# Ampli_FI2.net
KiCad netlist of a schematic drawn in Altium Designer
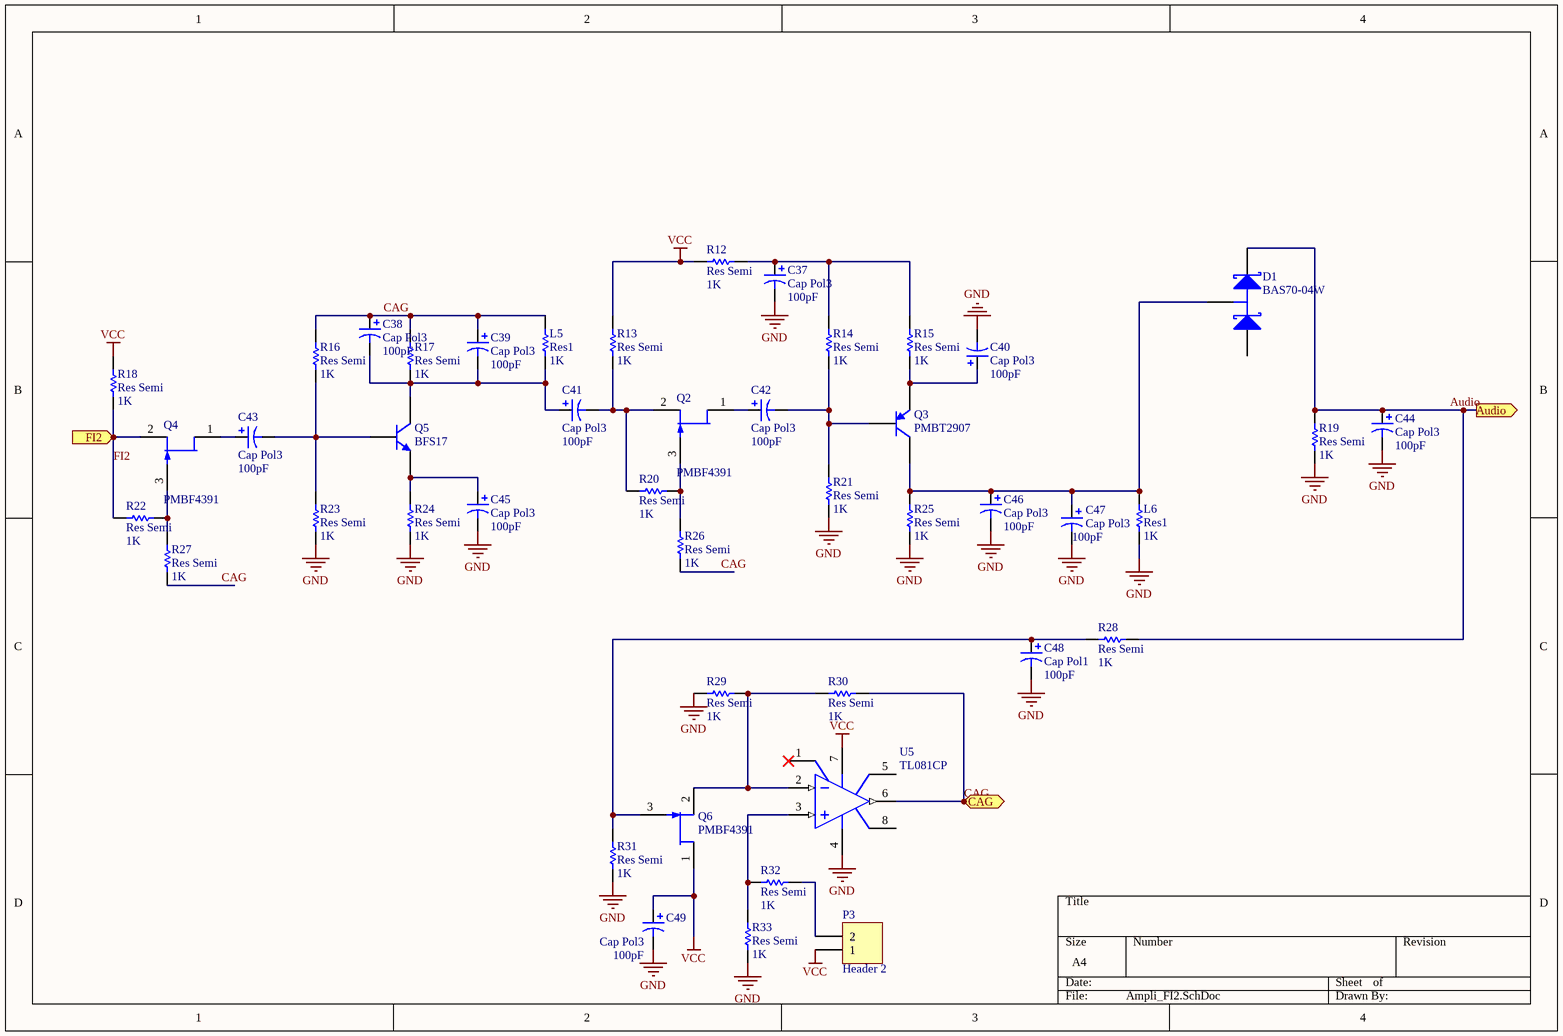
[diagram p0: Ampli_FI2.SchDoc]

(export (version "E")
  (design (tool "Eeschema 10.0.6"))
  (components
    (comp (ref "C37")
      (value "Cap Pol3")
      (footprint "C0805")
      (description "Polarized Capacitor (Surface Mount)")
      (fields (field (name "ALTIUM_VALUE") "100pF") (field (name "PUBLISHER") "Altium Limited"))
      (libsource (lib "Miscellaneous Devices") (part "Cap Pol3"))
    )
    (comp (ref "C38")
      (value "Cap Pol3")
      (footprint "C0805")
      (description "Polarized Capacitor (Surface Mount)")
      (fields (field (name "ALTIUM_VALUE") "100pF") (field (name "PUBLISHER") "Altium Limited"))
      (libsource (lib "Miscellaneous Devices") (part "Cap Pol3"))
    )
    (comp (ref "C39")
      (value "Cap Pol3")
      (footprint "C0805")
      (description "Polarized Capacitor (Surface Mount)")
      (fields (field (name "ALTIUM_VALUE") "100pF") (field (name "PUBLISHER") "Altium Limited"))
      (libsource (lib "Miscellaneous Devices") (part "Cap Pol3"))
    )
    (comp (ref "C40")
      (value "Cap Pol3")
      (footprint "C0805")
      (description "Polarized Capacitor (Surface Mount)")
      (fields (field (name "ALTIUM_VALUE") "100pF") (field (name "PUBLISHER") "Altium Limited"))
      (libsource (lib "Miscellaneous Devices") (part "Cap Pol3"))
    )
    (comp (ref "C41")
      (value "Cap Pol3")
      (footprint "C0805")
      (description "Polarized Capacitor (Surface Mount)")
      (fields (field (name "ALTIUM_VALUE") "100pF") (field (name "PUBLISHER") "Altium Limited"))
      (libsource (lib "Miscellaneous Devices") (part "Cap Pol3"))
    )
    (comp (ref "C42")
      (value "Cap Pol3")
      (footprint "C0805")
      (description "Polarized Capacitor (Surface Mount)")
      (fields (field (name "ALTIUM_VALUE") "100pF") (field (name "PUBLISHER") "Altium Limited"))
      (libsource (lib "Miscellaneous Devices") (part "Cap Pol3"))
    )
    (comp (ref "C43")
      (value "Cap Pol3")
      (footprint "C0805")
      (description "Polarized Capacitor (Surface Mount)")
      (fields (field (name "ALTIUM_VALUE") "100pF") (field (name "PUBLISHER") "Altium Limited"))
      (libsource (lib "Miscellaneous Devices") (part "Cap Pol3"))
    )
    (comp (ref "C44")
      (value "Cap Pol3")
      (footprint "C0805")
      (description "Polarized Capacitor (Surface Mount)")
      (fields (field (name "ALTIUM_VALUE") "100pF") (field (name "PUBLISHER") "Altium Limited"))
      (libsource (lib "Miscellaneous Devices") (part "Cap Pol3"))
    )
    (comp (ref "C45")
      (value "Cap Pol3")
      (footprint "C0805")
      (description "Polarized Capacitor (Surface Mount)")
      (fields (field (name "ALTIUM_VALUE") "100pF") (field (name "PUBLISHER") "Altium Limited"))
      (libsource (lib "Miscellaneous Devices") (part "Cap Pol3"))
    )
    (comp (ref "C46")
      (value "Cap Pol3")
      (footprint "C0805")
      (description "Polarized Capacitor (Surface Mount)")
      (fields (field (name "ALTIUM_VALUE") "100pF") (field (name "PUBLISHER") "Altium Limited"))
      (libsource (lib "Miscellaneous Devices") (part "Cap Pol3"))
    )
    (comp (ref "C47")
      (value "Cap Pol3")
      (footprint "C0805")
      (description "Polarized Capacitor (Surface Mount)")
      (fields (field (name "ALTIUM_VALUE") "100pF") (field (name "PUBLISHER") "Altium Limited"))
      (libsource (lib "Miscellaneous Devices") (part "Cap Pol3"))
    )
    (comp (ref "C48")
      (value "Cap Pol1")
      (footprint "B")
      (description "Polarized Capacitor (Radial)")
      (fields (field (name "ALTIUM_VALUE") "100pF") (field (name "PUBLISHER") "Altium Limited"))
      (libsource (lib "Miscellaneous Devices") (part "Cap Pol1"))
    )
    (comp (ref "C49")
      (value "Cap Pol3")
      (footprint "C0805")
      (description "Polarized Capacitor (Surface Mount)")
      (fields (field (name "ALTIUM_VALUE") "100pF") (field (name "PUBLISHER") "Altium Limited"))
      (libsource (lib "Miscellaneous Devices") (part "Cap Pol3"))
    )
    (comp (ref "D1")
      (value "BAS70-04W")
      (footprint "SOT323_N")
      (description "Schottky Barrier Double Diode")
      (fields (field (name "PUBLISHER") "Altium Limited"))
      (libsource (lib "Philips Discrete Diode - Schottky") (part "BAS70-04W"))
    )
    (comp (ref "L5")
      (value "Res1")
      (footprint "AXIAL-0.3")
      (description "Resistor")
      (fields (field (name "ALTIUM_VALUE") "1K") (field (name "PUBLISHER") "Altium Limited"))
      (libsource (lib "Miscellaneous Devices") (part "Res1"))
    )
    (comp (ref "L6")
      (value "Res1")
      (footprint "AXIAL-0.3")
      (description "Resistor")
      (fields (field (name "ALTIUM_VALUE") "1K") (field (name "PUBLISHER") "Altium Limited"))
      (libsource (lib "Miscellaneous Devices") (part "Res1"))
    )
    (comp (ref "P3")
      (value "Header 2")
      (footprint "HDR1X2")
      (description "Header, 2-Pin")
      (fields (field (name "PUBLISHER") "Altium Limited"))
      (libsource (lib "Miscellaneous Connectors") (part "Header 2"))
    )
    (comp (ref "Q2")
      (value "PMBF4391")
      (footprint "SOT23_N")
      (description "N-channel Silicon Junction Field-effect Transistor")
      (fields (field (name "PUBLISHER") "Altium Limited"))
      (libsource (lib "Philips Discrete JFET") (part "PMBF4391"))
    )
    (comp (ref "Q3")
      (value "PMBT2907")
      (footprint "SOT23_N")
      (description "PNP Switching Transistor")
      (fields (field (name "PUBLISHER") "Altium Limited"))
      (libsource (lib "Philips Discrete BJT - Low Power") (part "PMBT2907"))
    )
    (comp (ref "Q4")
      (value "PMBF4391")
      (footprint "SOT23_N")
      (description "N-channel Silicon Junction Field-effect Transistor")
      (fields (field (name "PUBLISHER") "Altium Limited"))
      (libsource (lib "Philips Discrete JFET") (part "PMBF4391"))
    )
    (comp (ref "Q5")
      (value "BFS17")
      (footprint "SOT23_N")
      (description "NPN 1 GHz Wideband Transistor")
      (fields (field (name "PUBLISHER") "Altium Limited"))
      (libsource (lib "Philips Discrete BJT - RF Transistor") (part "BFS17"))
    )
    (comp (ref "Q6")
      (value "PMBF4391")
      (footprint "SOT23_N")
      (description "N-channel Silicon Junction Field-effect Transistor")
      (fields (field (name "PUBLISHER") "Altium Limited"))
      (libsource (lib "Philips Discrete JFET") (part "PMBF4391"))
    )
    (comp (ref "R12")
      (value "Res Semi")
      (footprint "2012[0805]")
      (description "Semiconductor Resistor")
      (fields (field (name "ALTIUM_VALUE") "1K") (field (name "PUBLISHER") "Altium Limited"))
      (libsource (lib "Miscellaneous Devices") (part "Res Semi"))
    )
    (comp (ref "R13")
      (value "Res Semi")
      (footprint "2012[0805]")
      (description "Semiconductor Resistor")
      (fields (field (name "ALTIUM_VALUE") "1K") (field (name "PUBLISHER") "Altium Limited"))
      (libsource (lib "Miscellaneous Devices") (part "Res Semi"))
    )
    (comp (ref "R14")
      (value "Res Semi")
      (footprint "2012[0805]")
      (description "Semiconductor Resistor")
      (fields (field (name "ALTIUM_VALUE") "1K") (field (name "PUBLISHER") "Altium Limited"))
      (libsource (lib "Miscellaneous Devices") (part "Res Semi"))
    )
    (comp (ref "R15")
      (value "Res Semi")
      (footprint "2012[0805]")
      (description "Semiconductor Resistor")
      (fields (field (name "ALTIUM_VALUE") "1K") (field (name "PUBLISHER") "Altium Limited"))
      (libsource (lib "Miscellaneous Devices") (part "Res Semi"))
    )
    (comp (ref "R16")
      (value "Res Semi")
      (footprint "2012[0805]")
      (description "Semiconductor Resistor")
      (fields (field (name "ALTIUM_VALUE") "1K") (field (name "PUBLISHER") "Altium Limited"))
      (libsource (lib "Miscellaneous Devices") (part "Res Semi"))
    )
    (comp (ref "R17")
      (value "Res Semi")
      (footprint "2012[0805]")
      (description "Semiconductor Resistor")
      (fields (field (name "ALTIUM_VALUE") "1K") (field (name "PUBLISHER") "Altium Limited"))
      (libsource (lib "Miscellaneous Devices") (part "Res Semi"))
    )
    (comp (ref "R18")
      (value "Res Semi")
      (footprint "2012[0805]")
      (description "Semiconductor Resistor")
      (fields (field (name "ALTIUM_VALUE") "1K") (field (name "PUBLISHER") "Altium Limited"))
      (libsource (lib "Miscellaneous Devices") (part "Res Semi"))
    )
    (comp (ref "R19")
      (value "Res Semi")
      (footprint "2012[0805]")
      (description "Semiconductor Resistor")
      (fields (field (name "ALTIUM_VALUE") "1K") (field (name "PUBLISHER") "Altium Limited"))
      (libsource (lib "Miscellaneous Devices") (part "Res Semi"))
    )
    (comp (ref "R20")
      (value "Res Semi")
      (footprint "2012[0805]")
      (description "Semiconductor Resistor")
      (fields (field (name "ALTIUM_VALUE") "1K") (field (name "PUBLISHER") "Altium Limited"))
      (libsource (lib "Miscellaneous Devices") (part "Res Semi"))
    )
    (comp (ref "R21")
      (value "Res Semi")
      (footprint "2012[0805]")
      (description "Semiconductor Resistor")
      (fields (field (name "ALTIUM_VALUE") "1K") (field (name "PUBLISHER") "Altium Limited"))
      (libsource (lib "Miscellaneous Devices") (part "Res Semi"))
    )
    (comp (ref "R22")
      (value "Res Semi")
      (footprint "2012[0805]")
      (description "Semiconductor Resistor")
      (fields (field (name "ALTIUM_VALUE") "1K") (field (name "PUBLISHER") "Altium Limited"))
      (libsource (lib "Miscellaneous Devices") (part "Res Semi"))
    )
    (comp (ref "R23")
      (value "Res Semi")
      (footprint "2012[0805]")
      (description "Semiconductor Resistor")
      (fields (field (name "ALTIUM_VALUE") "1K") (field (name "PUBLISHER") "Altium Limited"))
      (libsource (lib "Miscellaneous Devices") (part "Res Semi"))
    )
    (comp (ref "R24")
      (value "Res Semi")
      (footprint "2012[0805]")
      (description "Semiconductor Resistor")
      (fields (field (name "ALTIUM_VALUE") "1K") (field (name "PUBLISHER") "Altium Limited"))
      (libsource (lib "Miscellaneous Devices") (part "Res Semi"))
    )
    (comp (ref "R25")
      (value "Res Semi")
      (footprint "2012[0805]")
      (description "Semiconductor Resistor")
      (fields (field (name "ALTIUM_VALUE") "1K") (field (name "PUBLISHER") "Altium Limited"))
      (libsource (lib "Miscellaneous Devices") (part "Res Semi"))
    )
    (comp (ref "R26")
      (value "Res Semi")
      (footprint "2012[0805]")
      (description "Semiconductor Resistor")
      (fields (field (name "ALTIUM_VALUE") "1K") (field (name "PUBLISHER") "Altium Limited"))
      (libsource (lib "Miscellaneous Devices") (part "Res Semi"))
    )
    (comp (ref "R27")
      (value "Res Semi")
      (footprint "2012[0805]")
      (description "Semiconductor Resistor")
      (fields (field (name "ALTIUM_VALUE") "1K") (field (name "PUBLISHER") "Altium Limited"))
      (libsource (lib "Miscellaneous Devices") (part "Res Semi"))
    )
    (comp (ref "R28")
      (value "Res Semi")
      (footprint "2012[0805]")
      (description "Semiconductor Resistor")
      (fields (field (name "ALTIUM_VALUE") "1K") (field (name "PUBLISHER") "Altium Limited"))
      (libsource (lib "Miscellaneous Devices") (part "Res Semi"))
    )
    (comp (ref "R29")
      (value "Res Semi")
      (footprint "2012[0805]")
      (description "Semiconductor Resistor")
      (fields (field (name "ALTIUM_VALUE") "1K") (field (name "PUBLISHER") "Altium Limited"))
      (libsource (lib "Miscellaneous Devices") (part "Res Semi"))
    )
    (comp (ref "R30")
      (value "Res Semi")
      (footprint "2012[0805]")
      (description "Semiconductor Resistor")
      (fields (field (name "ALTIUM_VALUE") "1K") (field (name "PUBLISHER") "Altium Limited"))
      (libsource (lib "Miscellaneous Devices") (part "Res Semi"))
    )
    (comp (ref "R31")
      (value "Res Semi")
      (footprint "2012[0805]")
      (description "Semiconductor Resistor")
      (fields (field (name "ALTIUM_VALUE") "1K") (field (name "PUBLISHER") "Altium Limited"))
      (libsource (lib "Miscellaneous Devices") (part "Res Semi"))
    )
    (comp (ref "R32")
      (value "Res Semi")
      (footprint "2012[0805]")
      (description "Semiconductor Resistor")
      (fields (field (name "ALTIUM_VALUE") "1K") (field (name "PUBLISHER") "Altium Limited"))
      (libsource (lib "Miscellaneous Devices") (part "Res Semi"))
    )
    (comp (ref "R33")
      (value "Res Semi")
      (footprint "2012[0805]")
      (description "Semiconductor Resistor")
      (fields (field (name "ALTIUM_VALUE") "1K") (field (name "PUBLISHER") "Altium Limited"))
      (libsource (lib "Miscellaneous Devices") (part "Res Semi"))
    )
    (comp (ref "U5")
      (value "TL081CP")
      (footprint "626-05")
      (description "JFET-Input Operational Amplifier")
      (fields (field (name "PUBLISHER") "Altium Limited"))
      (libsource (lib "Motorola Amplifier Operational Amplifier") (part "TL081CP"))
    )
  )
  (nets
    (net (code "1") (name "/Audio") (class "Default")
      (node (ref "C44") (pin "1") (pinfunction "1_1") (pintype "passive"))
      (node (ref "D1") (pin "2") (pinfunction "K_2") (pintype "passive"))
      (node (ref "R19") (pin "2") (pinfunction "2_2") (pintype "passive"))
      (node (ref "R28") (pin "1") (pinfunction "1_1") (pintype "passive"))
    )
    (net (code "2") (name "/CAG") (class "Default")
      (node (ref "C38") (pin "1") (pinfunction "1_1") (pintype "passive"))
      (node (ref "C39") (pin "1") (pinfunction "1_1") (pintype "passive"))
      (node (ref "L5") (pin "2") (pinfunction "2_2") (pintype "passive"))
      (node (ref "R16") (pin "2") (pinfunction "2_2") (pintype "passive"))
      (node (ref "R17") (pin "2") (pinfunction "2_2") (pintype "passive"))
      (node (ref "R26") (pin "2") (pinfunction "2_2") (pintype "passive"))
      (node (ref "R27") (pin "2") (pinfunction "2_2") (pintype "passive"))
      (node (ref "R30") (pin "2") (pinfunction "2_2") (pintype "passive"))
      (node (ref "U5") (pin "6") (pinfunction "OUT_6") (pintype "output"))
    )
    (net (code "3") (name "/FI2") (class "Default")
      (node (ref "Q4") (pin "2") (pinfunction "S_2") (pintype "passive"))
      (node (ref "R18") (pin "2") (pinfunction "2_2") (pintype "passive"))
      (node (ref "R22") (pin "1") (pinfunction "1_1") (pintype "passive"))
    )
    (net (code "4") (name "GND") (class "Default")
      (node (ref "C37") (pin "2") (pinfunction "2_2") (pintype "passive"))
      (node (ref "C40") (pin "2") (pinfunction "2_2") (pintype "passive"))
      (node (ref "C44") (pin "2") (pinfunction "2_2") (pintype "passive"))
      (node (ref "C45") (pin "2") (pinfunction "2_2") (pintype "passive"))
      (node (ref "C46") (pin "2") (pinfunction "2_2") (pintype "passive"))
      (node (ref "C47") (pin "2") (pinfunction "2_2") (pintype "passive"))
      (node (ref "C48") (pin "2") (pinfunction "2_2") (pintype "passive"))
      (node (ref "C49") (pin "2") (pinfunction "2_2") (pintype "passive"))
      (node (ref "L6") (pin "1") (pinfunction "1_1") (pintype "passive"))
      (node (ref "R19") (pin "1") (pinfunction "1_1") (pintype "passive"))
      (node (ref "R21") (pin "2") (pinfunction "2_2") (pintype "passive"))
      (node (ref "R23") (pin "1") (pinfunction "1_1") (pintype "passive"))
      (node (ref "R24") (pin "1") (pinfunction "1_1") (pintype "passive"))
      (node (ref "R25") (pin "2") (pinfunction "2_2") (pintype "passive"))
      (node (ref "R29") (pin "1") (pinfunction "1_1") (pintype "passive"))
      (node (ref "R31") (pin "2") (pinfunction "2_2") (pintype "passive"))
      (node (ref "R33") (pin "2") (pinfunction "2_2") (pintype "passive"))
      (node (ref "U5") (pin "4") (pinfunction "V-_4") (pintype "power_in"))
    )
    (net (code "5") (name "Net-(C37-Pad1)") (class "Default")
      (node (ref "C37") (pin "1") (pinfunction "1_1") (pintype "passive"))
      (node (ref "R12") (pin "1") (pinfunction "1_1") (pintype "passive"))
      (node (ref "R14") (pin "1") (pinfunction "1_1") (pintype "passive"))
      (node (ref "R15") (pin "1") (pinfunction "1_1") (pintype "passive"))
    )
    (net (code "6") (name "Net-(D1-C)") (class "Default")
      (node (ref "C46") (pin "1") (pinfunction "1_1") (pintype "passive"))
      (node (ref "C47") (pin "1") (pinfunction "1_1") (pintype "passive"))
      (node (ref "D1") (pin "3") (pinfunction "C_3") (pintype "passive"))
      (node (ref "L6") (pin "2") (pinfunction "2_2") (pintype "passive"))
      (node (ref "Q3") (pin "3") (pinfunction "C_3") (pintype "passive"))
      (node (ref "R25") (pin "1") (pinfunction "1_1") (pintype "passive"))
    )
    (net (code "7") (name "Net-(P3-Pad2)") (class "Default")
      (node (ref "P3") (pin "2") (pinfunction "2_2") (pintype "passive"))
      (node (ref "R32") (pin "1") (pinfunction "1_1") (pintype "passive"))
    )
    (net (code "8") (name "Net-(Q2-D)") (class "Default")
      (node (ref "C42") (pin "1") (pinfunction "1_1") (pintype "passive"))
      (node (ref "Q2") (pin "1") (pinfunction "D_1") (pintype "passive"))
    )
    (net (code "9") (name "Net-(Q2-G)") (class "Default")
      (node (ref "Q2") (pin "3") (pinfunction "G_3") (pintype "passive"))
      (node (ref "R20") (pin "2") (pinfunction "2_2") (pintype "passive"))
      (node (ref "R26") (pin "1") (pinfunction "1_1") (pintype "passive"))
    )
    (net (code "10") (name "Net-(Q2-S)") (class "Default")
      (node (ref "C41") (pin "2") (pinfunction "2_2") (pintype "passive"))
      (node (ref "Q2") (pin "2") (pinfunction "S_2") (pintype "passive"))
      (node (ref "R13") (pin "1") (pinfunction "1_1") (pintype "passive"))
      (node (ref "R20") (pin "1") (pinfunction "1_1") (pintype "passive"))
    )
    (net (code "11") (name "Net-(Q3-B)") (class "Default")
      (node (ref "C42") (pin "2") (pinfunction "2_2") (pintype "passive"))
      (node (ref "Q3") (pin "1") (pinfunction "B_1") (pintype "passive"))
      (node (ref "R14") (pin "2") (pinfunction "2_2") (pintype "passive"))
      (node (ref "R21") (pin "1") (pinfunction "1_1") (pintype "passive"))
    )
    (net (code "12") (name "Net-(Q3-E)") (class "Default")
      (node (ref "C40") (pin "1") (pinfunction "1_1") (pintype "passive"))
      (node (ref "Q3") (pin "2") (pinfunction "E_2") (pintype "passive"))
      (node (ref "R15") (pin "2") (pinfunction "2_2") (pintype "passive"))
    )
    (net (code "13") (name "Net-(Q4-D)") (class "Default")
      (node (ref "C43") (pin "1") (pinfunction "1_1") (pintype "passive"))
      (node (ref "Q4") (pin "1") (pinfunction "D_1") (pintype "passive"))
    )
    (net (code "14") (name "Net-(Q4-G)") (class "Default")
      (node (ref "Q4") (pin "3") (pinfunction "G_3") (pintype "passive"))
      (node (ref "R22") (pin "2") (pinfunction "2_2") (pintype "passive"))
      (node (ref "R27") (pin "1") (pinfunction "1_1") (pintype "passive"))
    )
    (net (code "15") (name "Net-(Q5-B)") (class "Default")
      (node (ref "C43") (pin "2") (pinfunction "2_2") (pintype "passive"))
      (node (ref "Q5") (pin "1") (pinfunction "B_1") (pintype "passive"))
      (node (ref "R16") (pin "1") (pinfunction "1_1") (pintype "passive"))
      (node (ref "R23") (pin "2") (pinfunction "2_2") (pintype "passive"))
    )
    (net (code "16") (name "Net-(Q5-C)") (class "Default")
      (node (ref "C38") (pin "2") (pinfunction "2_2") (pintype "passive"))
      (node (ref "C39") (pin "2") (pinfunction "2_2") (pintype "passive"))
      (node (ref "C41") (pin "1") (pinfunction "1_1") (pintype "passive"))
      (node (ref "L5") (pin "1") (pinfunction "1_1") (pintype "passive"))
      (node (ref "Q5") (pin "3") (pinfunction "C_3") (pintype "passive"))
      (node (ref "R17") (pin "1") (pinfunction "1_1") (pintype "passive"))
    )
    (net (code "17") (name "Net-(Q5-E)") (class "Default")
      (node (ref "C45") (pin "1") (pinfunction "1_1") (pintype "passive"))
      (node (ref "Q5") (pin "2") (pinfunction "E_2") (pintype "passive"))
      (node (ref "R24") (pin "2") (pinfunction "2_2") (pintype "passive"))
    )
    (net (code "18") (name "Net-(Q6-G)") (class "Default")
      (node (ref "C48") (pin "1") (pinfunction "1_1") (pintype "passive"))
      (node (ref "Q6") (pin "3") (pinfunction "G_3") (pintype "passive"))
      (node (ref "R28") (pin "2") (pinfunction "2_2") (pintype "passive"))
      (node (ref "R31") (pin "1") (pinfunction "1_1") (pintype "passive"))
    )
    (net (code "19") (name "Net-(Q6-S)") (class "Default")
      (node (ref "Q6") (pin "2") (pinfunction "S_2") (pintype "passive"))
      (node (ref "R29") (pin "2") (pinfunction "2_2") (pintype "passive"))
      (node (ref "R30") (pin "1") (pinfunction "1_1") (pintype "passive"))
      (node (ref "U5") (pin "2") (pinfunction "IN-_2") (pintype "input"))
    )
    (net (code "20") (name "Net-(U5-IN+)") (class "Default")
      (node (ref "R32") (pin "2") (pinfunction "2_2") (pintype "passive"))
      (node (ref "R33") (pin "1") (pinfunction "1_1") (pintype "passive"))
      (node (ref "U5") (pin "3") (pinfunction "IN+_3") (pintype "input"))
    )
    (net (code "21") (name "VCC") (class "Default")
      (node (ref "C49") (pin "1") (pinfunction "1_1") (pintype "passive"))
      (node (ref "P3") (pin "1") (pinfunction "1_1") (pintype "passive"))
      (node (ref "Q6") (pin "1") (pinfunction "D_1") (pintype "passive"))
      (node (ref "R12") (pin "2") (pinfunction "2_2") (pintype "passive"))
      (node (ref "R13") (pin "2") (pinfunction "2_2") (pintype "passive"))
      (node (ref "R18") (pin "1") (pinfunction "1_1") (pintype "passive"))
      (node (ref "U5") (pin "7") (pinfunction "V+_7") (pintype "power_in"))
    )
    (net (code "22") (name "unconnected-(D1-A-Pad1)") (class "Default")
      (node (ref "D1") (pin "1") (pinfunction "A_1") (pintype "passive"))
    )
    (net (code "23") (name "unconnected-(U5-NC-Pad8)") (class "Default")
      (node (ref "U5") (pin "8") (pinfunction "NC_8") (pintype "passive"))
    )
    (net (code "24") (name "unconnected-(U5-OS_NULL-Pad1)") (class "Default")
      (node (ref "U5") (pin "1") (pinfunction "OS_NULL_1") (pintype "passive+no_connect"))
    )
    (net (code "25") (name "unconnected-(U5-OS_NULL-Pad5)") (class "Default")
      (node (ref "U5") (pin "5") (pinfunction "OS_NULL_5") (pintype "passive"))
    )
  )
)
